# Display.net
KiCad netlist of a schematic drawn in Altium Designer
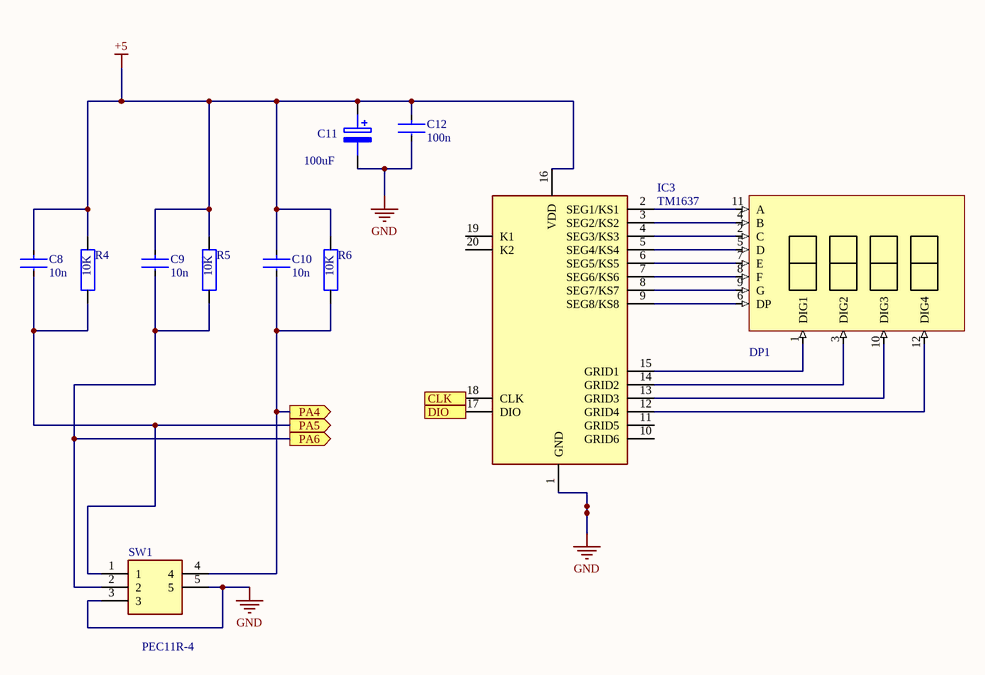
[diagram p0: Display.SchDoc]

(export (version "E")
  (design (tool "Eeschema 10.0.6"))
  (components
    (comp (ref "C8")
      (value "10n")
      (footprint "FP-C0805C-DN-IPC_A")
      (description "CAP CER 10000PF 200V X7R 0805")
      (fields
        (field (name "OCTOPART") "https://octopart.com/c0805c103k2ractu-kemet-9138347")
        (field (name "MANUFACTURER PART NUMBER") "C0805C103K2RACTU")
      )
      (libsource (lib "Altium Content Vault") (part "b4654b650e69147ec39a6b967a45e02"))
    )
    (comp (ref "C9")
      (value "10n")
      (footprint "FP-C0805C-DN-IPC_A")
      (description "CAP CER 10000PF 200V X7R 0805")
      (fields
        (field (name "OCTOPART") "https://octopart.com/c0805c103k2ractu-kemet-9138347")
        (field (name "MANUFACTURER PART NUMBER") "C0805C103K2RACTU")
      )
      (libsource (lib "Altium Content Vault") (part "b4654b650e69147ec39a6b967a45e02"))
    )
    (comp (ref "C10")
      (value "10n")
      (footprint "FP-C0805C-DN-IPC_A")
      (description "CAP CER 10000PF 200V X7R 0805")
      (fields
        (field (name "OCTOPART") "https://octopart.com/c0805c103k2ractu-kemet-9138347")
        (field (name "MANUFACTURER PART NUMBER") "C0805C103K2RACTU")
      )
      (libsource (lib "Altium Content Vault") (part "b4654b650e69147ec39a6b967a45e02"))
    )
    (comp (ref "C11")
      (value "100uF")
      (footprint "caprad100mil")
      (description "Capacitor Polarised")
      (fields
        (field (name "MANUFACTURER_PART_NUMBER") "T494D227K006AT")
        (field (name "MOUSER PART NUMBER") "80-T494D227K006")
      )
      (libsource (lib "soldeerstation") (part "ELCO220uF"))
    )
    (comp (ref "C12")
      (value "100n")
      (footprint "FP-C0805C-DN-IPC_A")
      (description "CAP CER 10000PF 200V X7R 0805")
      (fields
        (field (name "OCTOPART") "https://octopart.com/c0805c103k2ractu-kemet-9138347")
        (field (name "MANUFACTURER PART NUMBER") "C0805C103K2RACTU")
      )
      (libsource (lib "Altium Content Vault") (part "b4654b650e69147ec39a6b967a45e02"))
    )
    (comp (ref "DP1")
      (value "ELCO220uF")
      (footprint "display")
      (description "Capacitor Polarised")
      (fields
        (field (name "MANUFACTURER_PART_NUMBER") "T494D227K006AT")
        (field (name "MOUSER PART NUMBER") "80-T494D227K006")
      )
      (libsource (lib "soldeerstation") (part "Display"))
    )
    (comp (ref "IC3")
      (value "TM1637")
      (footprint "SamacSys:DIP778W53P254L2612H431Q20N")
      (description "Integrated Circuit")
      (libsource (lib "soldeerstation") (part "TM1637"))
    )
    (comp (ref "R4")
      (value "10K")
      (footprint "res0805ph")
      (description "Resistor")
      (fields (field (name "MANUFACTURER_PART_NUMBER") "CPF0201D10K2C1"))
      (libsource (lib "soldeerstation") (part "Res"))
    )
    (comp (ref "R5")
      (value "10K")
      (footprint "res0805ph")
      (description "Resistor")
      (fields (field (name "MANUFACTURER_PART_NUMBER") "CPF0201D10K2C1"))
      (libsource (lib "soldeerstation") (part "Res"))
    )
    (comp (ref "R6")
      (value "10K")
      (footprint "res0805ph")
      (description "Resistor")
      (fields (field (name "MANUFACTURER_PART_NUMBER") "CPF0201D10K2C1"))
      (libsource (lib "soldeerstation") (part "Res"))
    )
    (comp (ref "SW1")
      (value "PEC11R-4")
      (footprint "SamacSys:PEC12R-4XXXF-SXXXX_1")
      (description "Undefined or Miscellaneous")
      (fields
        (field (name "MOUSER2 PART NUMBER") "652-PEC11R-4225F-S24")
        (field (name "MANUFACTURER_PART_NUMBER") "PEC11R-4225F-S0024")
      )
      (libsource (lib "*") (part "PEC11R-4225F-S0024"))
    )
  )
  (nets
    (net (code "1") (name "+5") (class "Default")
      (node (ref "C10") (pin "1") (pinfunction "1_1") (pintype "passive"))
      (node (ref "C11") (pin "1") (pinfunction "+_1") (pintype "passive"))
      (node (ref "C12") (pin "1") (pinfunction "1_1") (pintype "passive"))
      (node (ref "C8") (pin "1") (pinfunction "1_1") (pintype "passive"))
      (node (ref "C9") (pin "1") (pinfunction "1_1") (pintype "passive"))
      (node (ref "IC3") (pin "16") (pinfunction "VDD_16") (pintype "passive"))
      (node (ref "R4") (pin "1") (pinfunction "1_1") (pintype "passive"))
      (node (ref "R5") (pin "1") (pinfunction "1_1") (pintype "passive"))
      (node (ref "R6") (pin "1") (pinfunction "1_1") (pintype "passive"))
    )
    (net (code "2") (name "/CLK") (class "Default")
      (node (ref "IC3") (pin "18") (pinfunction "CLK_18") (pintype "passive"))
    )
    (net (code "3") (name "/DIO") (class "Default")
      (node (ref "IC3") (pin "17") (pinfunction "DIO_17") (pintype "passive"))
    )
    (net (code "4") (name "/PA4") (class "Default")
      (node (ref "C10") (pin "2") (pinfunction "2_2") (pintype "passive"))
      (node (ref "R6") (pin "2") (pinfunction "2_2") (pintype "passive"))
      (node (ref "SW1") (pin "4") (pinfunction "4_4") (pintype "passive"))
    )
    (net (code "5") (name "/PA5") (class "Default")
      (node (ref "C8") (pin "2") (pinfunction "2_2") (pintype "passive"))
      (node (ref "R4") (pin "2") (pinfunction "2_2") (pintype "passive"))
      (node (ref "SW1") (pin "1") (pinfunction "1_1") (pintype "passive"))
    )
    (net (code "6") (name "/PA6") (class "Default")
      (node (ref "C9") (pin "2") (pinfunction "2_2") (pintype "passive"))
      (node (ref "R5") (pin "2") (pinfunction "2_2") (pintype "passive"))
      (node (ref "SW1") (pin "2") (pinfunction "2_2") (pintype "passive"))
    )
    (net (code "7") (name "GND") (class "Default")
      (node (ref "C11") (pin "2") (pinfunction "-_2") (pintype "passive"))
      (node (ref "C12") (pin "2") (pinfunction "2_2") (pintype "passive"))
      (node (ref "IC3") (pin "1") (pinfunction "GND_1") (pintype "passive"))
      (node (ref "SW1") (pin "3") (pinfunction "3_3") (pintype "passive"))
      (node (ref "SW1") (pin "5") (pinfunction "5_5") (pintype "passive"))
    )
    (net (code "8") (name "Net-(DP1-A)") (class "Default")
      (node (ref "DP1") (pin "11") (pinfunction "A_11") (pintype "input"))
      (node (ref "IC3") (pin "2") (pinfunction "SEG1/KS1_2") (pintype "passive"))
    )
    (net (code "9") (name "Net-(DP1-B)") (class "Default")
      (node (ref "DP1") (pin "4") (pinfunction "B_4") (pintype "input"))
      (node (ref "IC3") (pin "3") (pinfunction "SEG2/KS2_3") (pintype "passive"))
    )
    (net (code "10") (name "Net-(DP1-C)") (class "Default")
      (node (ref "DP1") (pin "2") (pinfunction "C_2") (pintype "input"))
      (node (ref "IC3") (pin "4") (pinfunction "SEG3/KS3_4") (pintype "passive"))
    )
    (net (code "11") (name "Net-(DP1-D)") (class "Default")
      (node (ref "DP1") (pin "5") (pinfunction "D_5") (pintype "input"))
      (node (ref "IC3") (pin "5") (pinfunction "SEG4/KS4_5") (pintype "passive"))
    )
    (net (code "12") (name "Net-(DP1-DIG1)") (class "Default")
      (node (ref "DP1") (pin "1") (pinfunction "DIG1_1") (pintype "input"))
      (node (ref "IC3") (pin "15") (pinfunction "GRID1_15") (pintype "passive"))
    )
    (net (code "13") (name "Net-(DP1-DIG2)") (class "Default")
      (node (ref "DP1") (pin "3") (pinfunction "DIG2_3") (pintype "input"))
      (node (ref "IC3") (pin "14") (pinfunction "GRID2_14") (pintype "passive"))
    )
    (net (code "14") (name "Net-(DP1-DIG3)") (class "Default")
      (node (ref "DP1") (pin "10") (pinfunction "DIG3_10") (pintype "input"))
      (node (ref "IC3") (pin "13") (pinfunction "GRID3_13") (pintype "passive"))
    )
    (net (code "15") (name "Net-(DP1-DIG4)") (class "Default")
      (node (ref "DP1") (pin "12") (pinfunction "DIG4_12") (pintype "input"))
      (node (ref "IC3") (pin "12") (pinfunction "GRID4_12") (pintype "passive"))
    )
    (net (code "16") (name "Net-(DP1-DP)") (class "Default")
      (node (ref "DP1") (pin "6") (pinfunction "DP_6") (pintype "input"))
      (node (ref "IC3") (pin "9") (pinfunction "SEG8/KS8_9") (pintype "passive"))
    )
    (net (code "17") (name "Net-(DP1-E)") (class "Default")
      (node (ref "DP1") (pin "7") (pinfunction "E_7") (pintype "input"))
      (node (ref "IC3") (pin "6") (pinfunction "SEG5/KS5_6") (pintype "passive"))
    )
    (net (code "18") (name "Net-(DP1-F)") (class "Default")
      (node (ref "DP1") (pin "8") (pinfunction "F_8") (pintype "input"))
      (node (ref "IC3") (pin "7") (pinfunction "SEG6/KS6_7") (pintype "passive"))
    )
    (net (code "19") (name "Net-(DP1-G)") (class "Default")
      (node (ref "DP1") (pin "9") (pinfunction "G_9") (pintype "input"))
      (node (ref "IC3") (pin "8") (pinfunction "SEG7/KS7_8") (pintype "passive"))
    )
    (net (code "20") (name "unconnected-(IC3-GRID5-Pad11)") (class "Default")
      (node (ref "IC3") (pin "11") (pinfunction "GRID5_11") (pintype "passive"))
    )
    (net (code "21") (name "unconnected-(IC3-GRID6-Pad10)") (class "Default")
      (node (ref "IC3") (pin "10") (pinfunction "GRID6_10") (pintype "passive"))
    )
    (net (code "22") (name "unconnected-(IC3-K1-Pad19)") (class "Default")
      (node (ref "IC3") (pin "19") (pinfunction "K1_19") (pintype "passive"))
    )
    (net (code "23") (name "unconnected-(IC3-K2-Pad20)") (class "Default")
      (node (ref "IC3") (pin "20") (pinfunction "K2_20") (pintype "passive"))
    )
  )
)
